# LIDO-HW_100_VinAndPower.net
KiCad netlist of a schematic drawn in Altium Designer
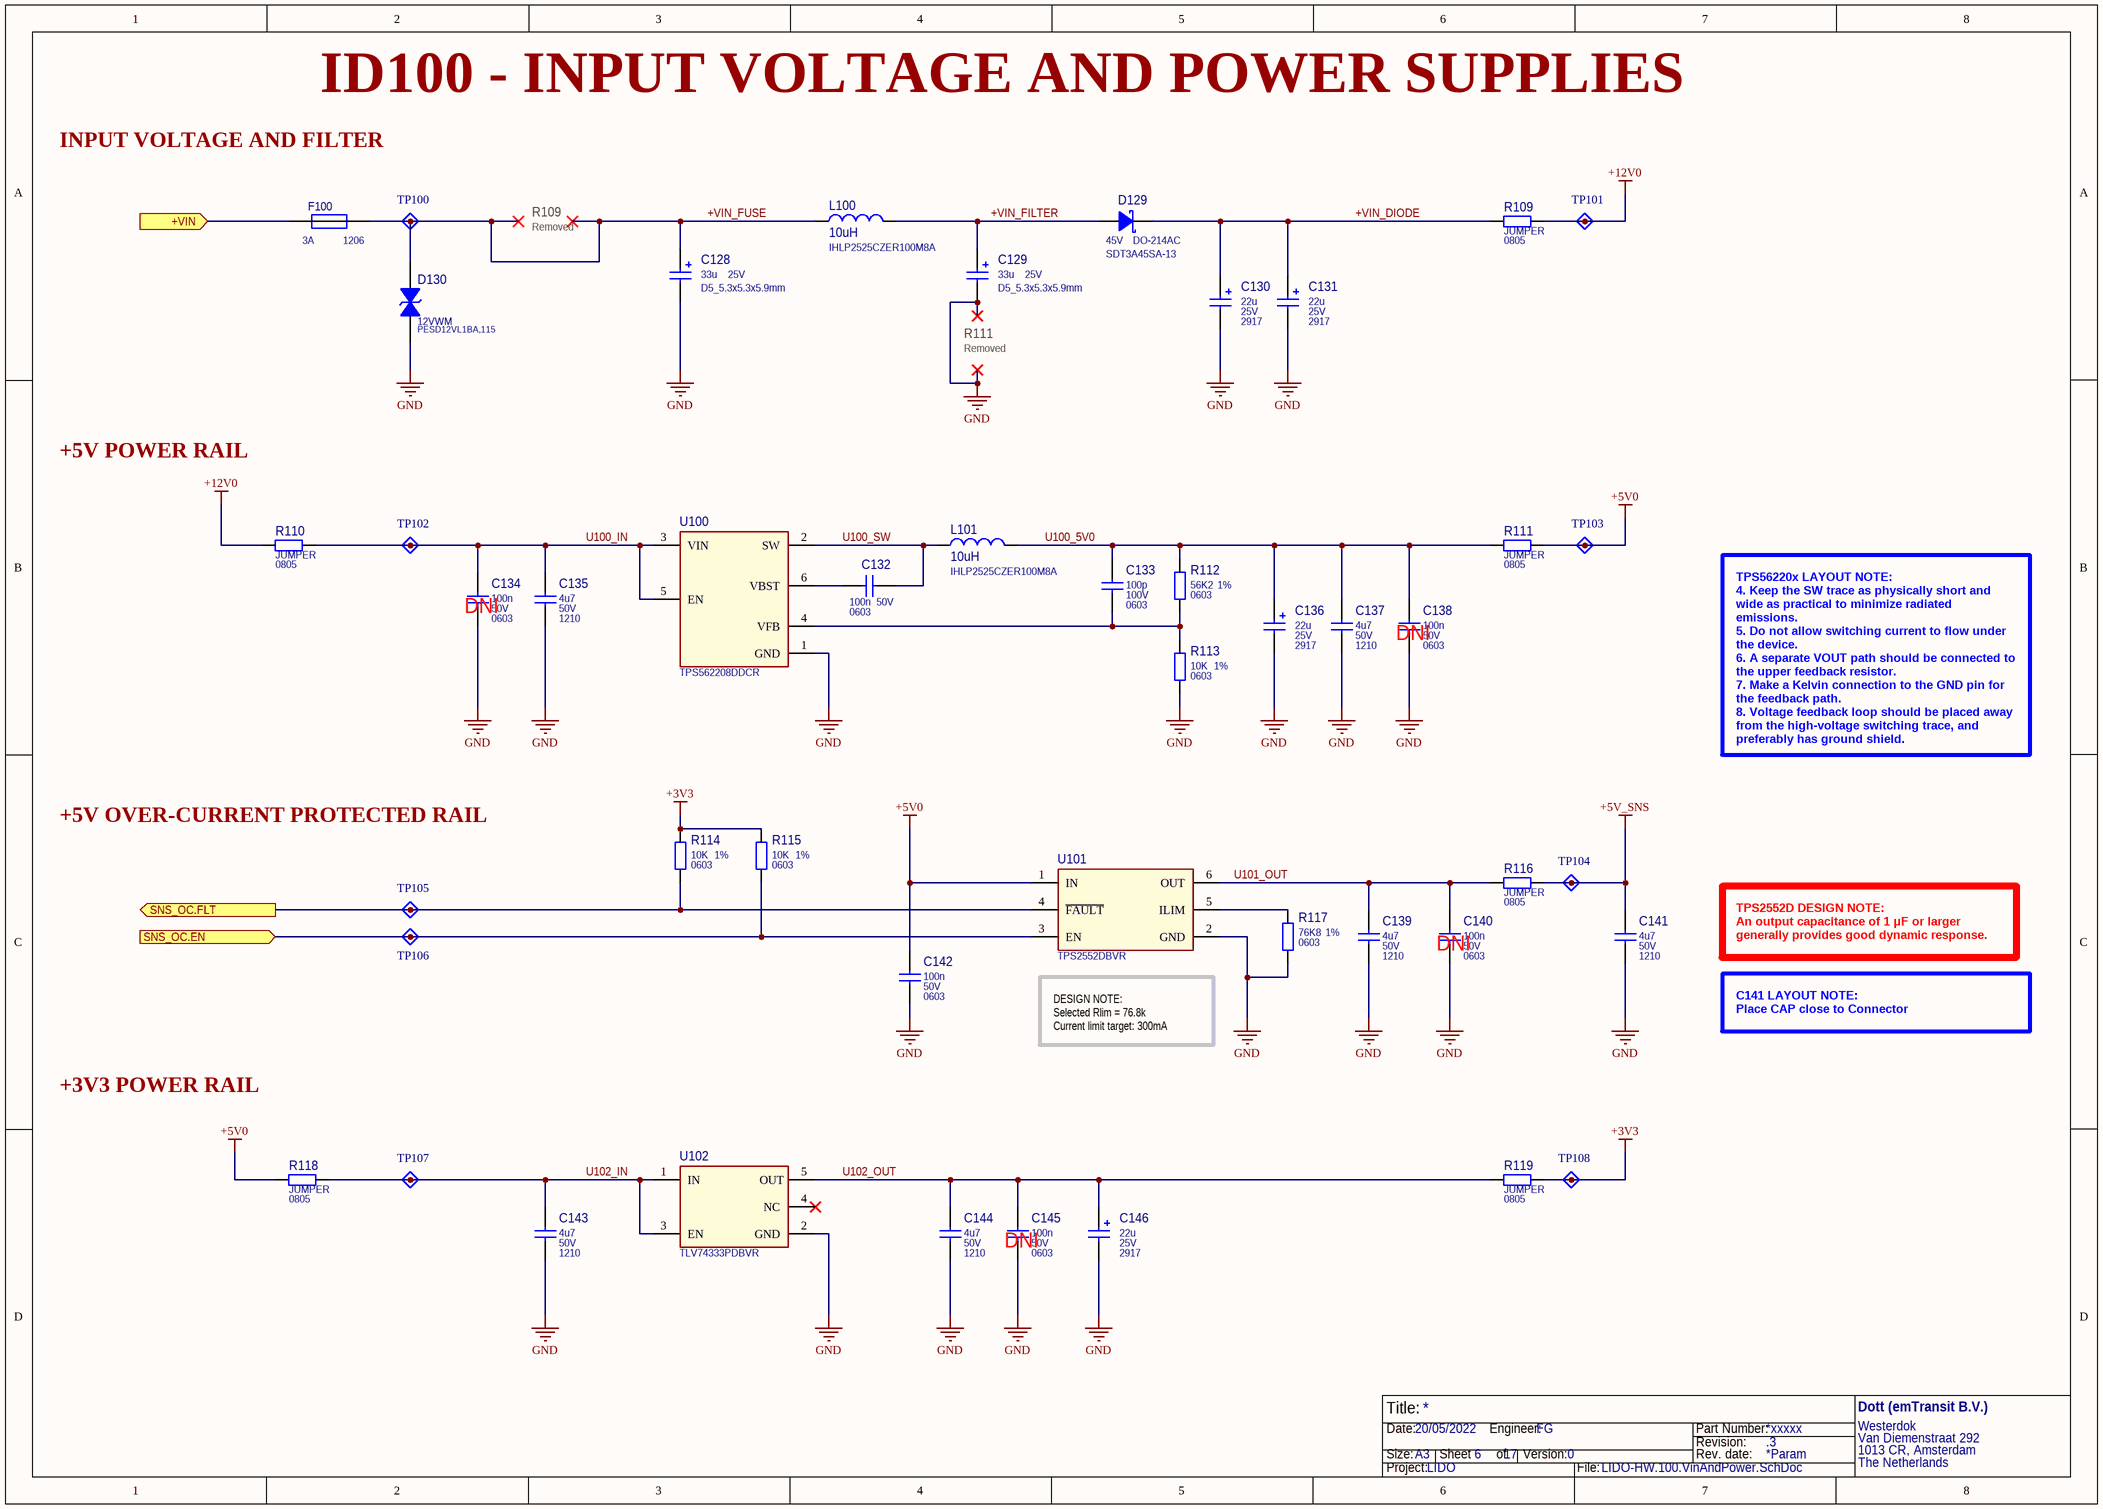
[diagram p0: LIDO-HW.100.VinAndPower.SchDoc]

(export (version "E")
  (design (tool "Eeschema 10.0.6"))
  (components
    (comp (ref "C128")
      (value "33u")
      (footprint "CAPAE_C_530X590L22X7-N_PANASONIC_A")
      (description "CAP ALUM POLY 33UF 20% 25V SMD")
      (fields
        (field (name "MANUFACTURER PART NUMBER") "25SVPK33M")
        (field (name "MANUFACTURER") "Panasonic Electronic Components")
        (field (name "PART VALUE 2") "25V")
        (field (name "PART PACKAGE") "D5_5.3x5.3x5.9mm")
      )
      (libsource (lib "DB_Library") (part "Polarized"))
    )
    (comp (ref "C129")
      (value "33u")
      (footprint "CAPAE_C_530X590L22X7-N_PANASONIC_A")
      (description "CAP ALUM POLY 33UF 20% 25V SMD")
      (fields
        (field (name "MANUFACTURER PART NUMBER") "25SVPK33M")
        (field (name "MANUFACTURER") "Panasonic Electronic Components")
        (field (name "PART VALUE 2") "25V")
        (field (name "PART PACKAGE") "D5_5.3x5.3x5.9mm")
      )
      (libsource (lib "DB_Library") (part "Polarized"))
    )
    (comp (ref "C130")
      (value "22u")
      (footprint "CAP_2917_7343X140-N_MURATA_A")
      (description "CAP ALUM POLY 22UF 20% 25V SMD")
      (fields
        (field (name "MANUFACTURER PART NUMBER") "ECASD31E226M040KA0")
        (field (name "MANUFACTURER") "Murata Electronics")
        (field (name "PART VALUE 2") "25V")
        (field (name "PART PACKAGE") "2917")
      )
      (libsource (lib "DB_Library") (part "Polarized"))
    )
    (comp (ref "C131")
      (value "22u")
      (footprint "CAP_2917_7343X140-N_MURATA_A")
      (description "CAP ALUM POLY 22UF 20% 25V SMD")
      (fields
        (field (name "MANUFACTURER PART NUMBER") "ECASD31E226M040KA0")
        (field (name "MANUFACTURER") "Murata Electronics")
        (field (name "PART VALUE 2") "25V")
        (field (name "PART PACKAGE") "2917")
      )
      (libsource (lib "DB_Library") (part "Polarized"))
    )
    (comp (ref "C132")
      (value "100n")
      (footprint "CAP_0603_1608X90-N_MURATA_A")
      (description "CAP CER 0.1UF 50V X7R 0603")
      (fields
        (field (name "MANUFACTURER PART NUMBER") "CGA3E2X7R1H104K080AA")
        (field (name "MANUFACTURER") "TDK Corporation")
        (field (name "PART VALUE 2") "50V")
        (field (name "PART PACKAGE") "0603")
      )
      (libsource (lib "DB_Library") (part "Ceramic"))
    )
    (comp (ref "C133")
      (value "100p")
      (footprint "CAP_0603_1608X90-N_MURATA_A")
      (description "CAP CER 100PF 100V C0G 0603")
      (fields
        (field (name "MANUFACTURER PART NUMBER") "CGA3E2C0G2A101J080AA")
        (field (name "MANUFACTURER") "TDK Corporation")
        (field (name "PART VALUE 2") "100V")
        (field (name "PART PACKAGE") "0603")
      )
      (libsource (lib "DB_Library") (part "Ceramic"))
    )
    (comp (ref "C134")
      (value "100n")
      (footprint "CAP_0603_1608X90-N_MURATA_A")
      (description "CAP CER 0.1UF 50V X7R 0603")
      (fields
        (field (name "MANUFACTURER PART NUMBER") "CGA3E2X7R1H104K080AA")
        (field (name "MANUFACTURER") "TDK Corporation")
        (field (name "PART VALUE 2") "50V")
        (field (name "PART PACKAGE") "0603")
      )
      (libsource (lib "DB_Library") (part "Ceramic"))
    )
    (comp (ref "C135")
      (value "4u7")
      (footprint "CAP_1210_3225X180-N_MURATA_A")
      (description "CAP CER 4.7UF 50V X7R 1210")
      (fields
        (field (name "MANUFACTURER PART NUMBER") "CL32B475KBJVPNE")
        (field (name "MANUFACTURER") "Samsung Electro-Mechanics")
        (field (name "PART VALUE 2") "50V")
        (field (name "PART PACKAGE") "1210")
      )
      (libsource (lib "DB_Library") (part "Ceramic"))
    )
    (comp (ref "C136")
      (value "22u")
      (footprint "CAP_2917_7343X140-N_MURATA_A")
      (description "CAP ALUM POLY 22UF 20% 25V SMD")
      (fields
        (field (name "MANUFACTURER PART NUMBER") "ECASD31E226M040KA0")
        (field (name "MANUFACTURER") "Murata Electronics")
        (field (name "PART VALUE 2") "25V")
        (field (name "PART PACKAGE") "2917")
      )
      (libsource (lib "DB_Library") (part "Polarized"))
    )
    (comp (ref "C137")
      (value "4u7")
      (footprint "CAP_1210_3225X180-N_MURATA_A")
      (description "CAP CER 4.7UF 50V X7R 1210")
      (fields
        (field (name "MANUFACTURER PART NUMBER") "CL32B475KBJVPNE")
        (field (name "MANUFACTURER") "Samsung Electro-Mechanics")
        (field (name "PART VALUE 2") "50V")
        (field (name "PART PACKAGE") "1210")
      )
      (libsource (lib "DB_Library") (part "Ceramic"))
    )
    (comp (ref "C138")
      (value "100n")
      (footprint "CAP_0603_1608X90-N_MURATA_A")
      (description "CAP CER 0.1UF 50V X7R 0603")
      (fields
        (field (name "MANUFACTURER PART NUMBER") "CGA3E2X7R1H104K080AA")
        (field (name "MANUFACTURER") "TDK Corporation")
        (field (name "PART VALUE 2") "50V")
        (field (name "PART PACKAGE") "0603")
      )
      (libsource (lib "DB_Library") (part "Ceramic"))
    )
    (comp (ref "C139")
      (value "4u7")
      (footprint "CAP_1210_3225X180-N_MURATA_A")
      (description "CAP CER 4.7UF 50V X7R 1210")
      (fields
        (field (name "MANUFACTURER PART NUMBER") "CL32B475KBJVPNE")
        (field (name "MANUFACTURER") "Samsung Electro-Mechanics")
        (field (name "PART VALUE 2") "50V")
        (field (name "PART PACKAGE") "1210")
      )
      (libsource (lib "DB_Library") (part "Ceramic"))
    )
    (comp (ref "C140")
      (value "100n")
      (footprint "CAP_0603_1608X90-N_MURATA_A")
      (description "CAP CER 0.1UF 50V X7R 0603")
      (fields
        (field (name "MANUFACTURER PART NUMBER") "CGA3E2X7R1H104K080AA")
        (field (name "MANUFACTURER") "TDK Corporation")
        (field (name "PART VALUE 2") "50V")
        (field (name "PART PACKAGE") "0603")
      )
      (libsource (lib "DB_Library") (part "Ceramic"))
    )
    (comp (ref "C141")
      (value "4u7")
      (footprint "CAP_1210_3225X180-N_MURATA_A")
      (description "CAP CER 4.7UF 50V X7R 1210")
      (fields
        (field (name "MANUFACTURER PART NUMBER") "CL32B475KBJVPNE")
        (field (name "MANUFACTURER") "Samsung Electro-Mechanics")
        (field (name "PART VALUE 2") "50V")
        (field (name "PART PACKAGE") "1210")
      )
      (libsource (lib "DB_Library") (part "Ceramic"))
    )
    (comp (ref "C142")
      (value "100n")
      (footprint "CAP_0603_1608X90-N_MURATA_A")
      (description "CAP CER 0.1UF 50V X7R 0603")
      (fields
        (field (name "MANUFACTURER PART NUMBER") "CGA3E2X7R1H104K080AA")
        (field (name "MANUFACTURER") "TDK Corporation")
        (field (name "PART VALUE 2") "50V")
        (field (name "PART PACKAGE") "0603")
      )
      (libsource (lib "DB_Library") (part "Ceramic"))
    )
    (comp (ref "C143")
      (value "4u7")
      (footprint "CAP_1210_3225X180-N_MURATA_A")
      (description "CAP CER 4.7UF 50V X7R 1210")
      (fields
        (field (name "MANUFACTURER PART NUMBER") "CL32B475KBJVPNE")
        (field (name "MANUFACTURER") "Samsung Electro-Mechanics")
        (field (name "PART VALUE 2") "50V")
        (field (name "PART PACKAGE") "1210")
      )
      (libsource (lib "DB_Library") (part "Ceramic"))
    )
    (comp (ref "C144")
      (value "4u7")
      (footprint "CAP_1210_3225X180-N_MURATA_A")
      (description "CAP CER 4.7UF 50V X7R 1210")
      (fields
        (field (name "MANUFACTURER PART NUMBER") "CL32B475KBJVPNE")
        (field (name "MANUFACTURER") "Samsung Electro-Mechanics")
        (field (name "PART VALUE 2") "50V")
        (field (name "PART PACKAGE") "1210")
      )
      (libsource (lib "DB_Library") (part "Ceramic"))
    )
    (comp (ref "C145")
      (value "100n")
      (footprint "CAP_0603_1608X90-N_MURATA_A")
      (description "CAP CER 0.1UF 50V X7R 0603")
      (fields
        (field (name "MANUFACTURER PART NUMBER") "CGA3E2X7R1H104K080AA")
        (field (name "MANUFACTURER") "TDK Corporation")
        (field (name "PART VALUE 2") "50V")
        (field (name "PART PACKAGE") "0603")
      )
      (libsource (lib "DB_Library") (part "Ceramic"))
    )
    (comp (ref "C146")
      (value "22u")
      (footprint "CAP_2917_7343X140-N_MURATA_A")
      (description "CAP ALUM POLY 22UF 20% 25V SMD")
      (fields
        (field (name "MANUFACTURER PART NUMBER") "ECASD31E226M040KA0")
        (field (name "MANUFACTURER") "Murata Electronics")
        (field (name "PART VALUE 2") "25V")
        (field (name "PART PACKAGE") "2917")
      )
      (libsource (lib "DB_Library") (part "Polarized"))
    )
    (comp (ref "D129")
      (value "45V")
      (footprint "DIOM519X260X240L114X145-N_WURTH_A")
      (description "SCHOTTKY RECTIFIER SMA T&R 10K")
      (fields
        (field (name "MANUFACTURER PART NUMBER") "SDT3A45SA-13")
        (field (name "MANUFACTURER") "Diodes Incorporated")
        (field (name "PART PACKAGE") "DO-214AC")
        (field (name "OBSOLETE PART") "False")
      )
      (libsource (lib "DB_Library") (part "Schottky_A"))
    )
    (comp (ref "D130")
      (value "12VWM")
      (footprint "NXP_SOD-323_250X125X95L30x32_A")
      (description "37V Clamp 5A (8/20µs) Ipp Tvs Diode Surface Mount SOD-323")
      (fields
        (field (name "MANUFACTURER PART NUMBER") "PESD12VL1BA,115")
        (field (name "MANUFACTURER") "Nexperia USA Inc.")
        (field (name "PART VALUE") "12VWM")
        (field (name "OBSOLETE PART") "False")
      )
      (libsource (lib "DB_Library") (part "BI-TVS_DIODE_B"))
    )
    (comp (ref "F100")
      (value "3A")
      (footprint "FUSE_1206-N_YAGEO_A")
      (description "3 A 125 V AC 63 V DC Fuse Board Mount (Cartridge Style Excluded) Surface Mount 1206 (3216 Metric)")
      (fields
        (field (name "MANUFACTURER PART NUMBER") "C1Q 3")
        (field (name "MANUFACTURER") "Bel Fuse Inc.")
        (field (name "PART PACKAGE") "1206")
      )
      (libsource (lib "DB_Library") (part "Fuse"))
    )
    (comp (ref "L100")
      (value "10uH")
      (footprint "VISHAY_IHLP2525CZ_647X647X300_A")
      (description "FIXED IND 10UH 4A 76.9 MOHM SMD")
      (fields
        (field (name "MANUFACTURER PART NUMBER") "IHLP2525CZER100M8A")
        (field (name "MANUFACTURER") "Vishay Dale")
        (field (name "OBSOLETE PART") "False")
      )
      (libsource (lib "DB_Library") (part "Inductor"))
    )
    (comp (ref "L101")
      (value "10uH")
      (footprint "VISHAY_IHLP2525CZ_647X647X300_A")
      (description "FIXED IND 10UH 4A 76.9 MOHM SMD")
      (fields
        (field (name "MANUFACTURER PART NUMBER") "IHLP2525CZER100M8A")
        (field (name "MANUFACTURER") "Vishay Dale")
        (field (name "OBSOLETE PART") "False")
      )
      (libsource (lib "DB_Library") (part "Inductor"))
    )
    (comp (ref "R109")
      (value "JUMPER")
      (footprint "RES_0805_2012X65-N_YAGEO_A")
      (description "RES SMD 0 OHM JUMPER 1/8W 0805")
      (fields
        (field (name "MANUFACTURER PART NUMBER") "ERJ-6GEY0R00V")
        (field (name "MANUFACTURER") "Panasonic Electronic Components")
        (field (name "PART PACKAGE") "0805")
      )
      (libsource (lib "") (part "Resistor_1"))
    )
    (comp (ref "R110")
      (value "JUMPER")
      (footprint "RES_0805_2012X65-N_YAGEO_A")
      (description "RES SMD 0 OHM JUMPER 1/8W 0805")
      (fields
        (field (name "MANUFACTURER PART NUMBER") "ERJ-6GEY0R00V")
        (field (name "MANUFACTURER") "Panasonic Electronic Components")
        (field (name "PART PACKAGE") "0805")
      )
      (libsource (lib "") (part "Resistor_1"))
    )
    (comp (ref "R111")
      (value "JUMPER")
      (footprint "RES_0805_2012X65-N_YAGEO_A")
      (description "RES SMD 0 OHM JUMPER 1/8W 0805")
      (fields
        (field (name "MANUFACTURER PART NUMBER") "ERJ-6GEY0R00V")
        (field (name "MANUFACTURER") "Panasonic Electronic Components")
        (field (name "PART PACKAGE") "0805")
      )
      (libsource (lib "") (part "Resistor_1"))
    )
    (comp (ref "R112")
      (value "56K2")
      (footprint "RES_0603_1608X60-N_YAGEO_A")
      (description "RES SMD 56.2K OHM 1% 1/10W 0603")
      (fields
        (field (name "MANUFACTURER PART NUMBER") "ERJ-3EKF5622V")
        (field (name "MANUFACTURER") "Panasonic Electronic Components")
        (field (name "PART VALUE 2") "1%")
        (field (name "PART PACKAGE") "0603")
      )
      (libsource (lib "DB_Library") (part "Resistor"))
    )
    (comp (ref "R113")
      (value "10K")
      (footprint "RES_0603_1608X60-N_YAGEO_A")
      (description "RES 10K OHM 1% 1/10W 0603")
      (fields
        (field (name "MANUFACTURER PART NUMBER") "RC0603FR-0710KL")
        (field (name "MANUFACTURER") "YAGEO")
        (field (name "PART VALUE 2") "1%")
        (field (name "PART PACKAGE") "0603")
      )
      (libsource (lib "DB_Library") (part "Resistor"))
    )
    (comp (ref "R114")
      (value "10K")
      (footprint "RES_0603_1608X60-N_YAGEO_A")
      (description "RES 10K OHM 1% 1/10W 0603")
      (fields
        (field (name "MANUFACTURER PART NUMBER") "RC0603FR-0710KL")
        (field (name "MANUFACTURER") "YAGEO")
        (field (name "PART VALUE 2") "1%")
        (field (name "PART PACKAGE") "0603")
      )
      (libsource (lib "DB_Library") (part "Resistor"))
    )
    (comp (ref "R115")
      (value "10K")
      (footprint "RES_0603_1608X60-N_YAGEO_A")
      (description "RES 10K OHM 1% 1/10W 0603")
      (fields
        (field (name "MANUFACTURER PART NUMBER") "RC0603FR-0710KL")
        (field (name "MANUFACTURER") "YAGEO")
        (field (name "PART VALUE 2") "1%")
        (field (name "PART PACKAGE") "0603")
      )
      (libsource (lib "DB_Library") (part "Resistor"))
    )
    (comp (ref "R116")
      (value "JUMPER")
      (footprint "RES_0805_2012X65-N_YAGEO_A")
      (description "RES SMD 0 OHM JUMPER 1/8W 0805")
      (fields
        (field (name "MANUFACTURER PART NUMBER") "ERJ-6GEY0R00V")
        (field (name "MANUFACTURER") "Panasonic Electronic Components")
        (field (name "PART PACKAGE") "0805")
      )
      (libsource (lib "") (part "Resistor_1"))
    )
    (comp (ref "R117")
      (value "76K8")
      (footprint "RES_0603_1608X60-N_YAGEO_A")
      (description "RES SMD 76.8K OHM 1% 1/10W 0603")
      (fields
        (field (name "MANUFACTURER PART NUMBER") "ERJ-3EKF7682V")
        (field (name "MANUFACTURER") "Panasonic Electronic Components")
        (field (name "PART VALUE 2") "1%")
        (field (name "PART PACKAGE") "0603")
      )
      (libsource (lib "DB_Library") (part "Resistor"))
    )
    (comp (ref "R118")
      (value "JUMPER")
      (footprint "RES_0805_2012X65-N_YAGEO_A")
      (description "RES SMD 0 OHM JUMPER 1/8W 0805")
      (fields
        (field (name "MANUFACTURER PART NUMBER") "ERJ-6GEY0R00V")
        (field (name "MANUFACTURER") "Panasonic Electronic Components")
        (field (name "PART PACKAGE") "0805")
      )
      (libsource (lib "") (part "Resistor_1"))
    )
    (comp (ref "R119")
      (value "JUMPER")
      (footprint "RES_0805_2012X65-N_YAGEO_A")
      (description "RES SMD 0 OHM JUMPER 1/8W 0805")
      (fields
        (field (name "MANUFACTURER PART NUMBER") "ERJ-6GEY0R00V")
        (field (name "MANUFACTURER") "Panasonic Electronic Components")
        (field (name "PART PACKAGE") "0805")
      )
      (libsource (lib "") (part "Resistor_1"))
    )
    (comp (ref "TP100")
      (value "TestPoint_A")
      (footprint "TESTPOINT_1D_A")
      (description "Pad Diamater 1mm")
      (fields (field (name "PART") "Test Point 1D A") (field (name "OBSOLETE PART") "False"))
      (libsource (lib "DB_Library") (part "TestPoint_A"))
    )
    (comp (ref "TP101")
      (value "TestPoint_A")
      (footprint "TESTPOINT_1D_A")
      (description "Pad Diamater 1mm")
      (fields (field (name "PART") "Test Point 1D A") (field (name "OBSOLETE PART") "False"))
      (libsource (lib "DB_Library") (part "TestPoint_A"))
    )
    (comp (ref "TP102")
      (value "TestPoint_A")
      (footprint "TESTPOINT_1D_A")
      (description "Pad Diamater 1mm")
      (fields (field (name "PART") "Test Point 1D A") (field (name "OBSOLETE PART") "False"))
      (libsource (lib "DB_Library") (part "TestPoint_A"))
    )
    (comp (ref "TP103")
      (value "TestPoint_A")
      (footprint "TESTPOINT_1D_A")
      (description "Pad Diamater 1mm")
      (fields (field (name "PART") "Test Point 1D A") (field (name "OBSOLETE PART") "False"))
      (libsource (lib "DB_Library") (part "TestPoint_A"))
    )
    (comp (ref "TP104")
      (value "TestPoint_A")
      (footprint "TESTPOINT_1D_A")
      (description "Pad Diamater 1mm")
      (fields (field (name "PART") "Test Point 1D A") (field (name "OBSOLETE PART") "False"))
      (libsource (lib "DB_Library") (part "TestPoint_A"))
    )
    (comp (ref "TP105")
      (value "TestPoint_A")
      (footprint "TESTPOINT_1D_A")
      (description "Pad Diamater 1mm")
      (fields (field (name "PART") "Test Point 1D A") (field (name "OBSOLETE PART") "False"))
      (libsource (lib "DB_Library") (part "TestPoint_A"))
    )
    (comp (ref "TP106")
      (value "TestPoint_A")
      (footprint "TESTPOINT_1D_A")
      (description "Pad Diamater 1mm")
      (fields (field (name "PART") "Test Point 1D A") (field (name "OBSOLETE PART") "False"))
      (libsource (lib "DB_Library") (part "TestPoint_A"))
    )
    (comp (ref "TP107")
      (value "TestPoint_A")
      (footprint "TESTPOINT_1D_A")
      (description "Pad Diamater 1mm")
      (fields (field (name "PART") "Test Point 1D A") (field (name "OBSOLETE PART") "False"))
      (libsource (lib "DB_Library") (part "TestPoint_A"))
    )
    (comp (ref "TP108")
      (value "TestPoint_A")
      (footprint "TESTPOINT_1D_A")
      (description "Pad Diamater 1mm")
      (fields (field (name "PART") "Test Point 1D A") (field (name "OBSOLETE PART") "False"))
      (libsource (lib "DB_Library") (part "TestPoint_A"))
    )
    (comp (ref "U100")
      (value "TPS562208DDCR")
      (footprint "SOT23-6P95_280X145L45-N_MICROCHIP_A")
      (description "Buck Switching Regulator IC Positive Adjustable 0.768V 1 Output 2A SOT-23-6 Thin, TSOT-23-6")
      (fields (field (name "MANUFACTURER") "Texas Instruments") (field (name "OBSOLETE PART") "False"))
      (libsource (lib "DB_Library") (part "TPS562208_A"))
    )
    (comp (ref "U101")
      (value "TPS2552DBVR")
      (footprint "SOT23-6P95_280X145L45-N_MICROCHIP_A")
      (description "Power Switch/Driver 1:1 N-Channel 1.5A SOT-23-6")
      (fields (field (name "MANUFACTURER") "Texas Instruments") (field (name "OBSOLETE PART") "False"))
      (libsource (lib "DB_Library") (part "TPS2552_A"))
    )
    (comp (ref "U102")
      (value "TLV74333PDBVR")
      (footprint "SOT23-5P95_280X145L45-N_TI_A")
      (description "Linear Voltage Regulator IC Positive Fixed 1 Output 300mA SOT-23-5")
      (fields (field (name "MANUFACTURER") "Texas Instruments") (field (name "OBSOLETE PART") "False"))
      (libsource (lib "DB_Library") (part "TLV74333PD_A"))
    )
  )
  (nets
    (net (code "1") (name "+3V3") (class "Default")
      (node (ref "R114") (pin "2") (pinfunction "2_2") (pintype "passive"))
      (node (ref "R115") (pin "2") (pinfunction "2_2") (pintype "passive"))
      (node (ref "R119") (pin "2") (pinfunction "2_2") (pintype "passive"))
      (node (ref "TP108") (pin "1") (pinfunction "TP_1") (pintype "passive"))
    )
    (net (code "2") (name "+5V0") (class "Default")
      (node (ref "C142") (pin "2") (pinfunction "2_2") (pintype "passive"))
      (node (ref "R111") (pin "2") (pinfunction "2_2") (pintype "passive"))
      (node (ref "R118") (pin "1") (pinfunction "1_1") (pintype "passive"))
      (node (ref "TP103") (pin "1") (pinfunction "TP_1") (pintype "passive"))
      (node (ref "U101") (pin "1") (pinfunction "IN_1") (pintype "power_in"))
    )
    (net (code "3") (name "+5V_SNS") (class "Default")
      (node (ref "C141") (pin "1") (pinfunction "1_1") (pintype "passive"))
      (node (ref "R116") (pin "2") (pinfunction "2_2") (pintype "passive"))
      (node (ref "TP104") (pin "1") (pinfunction "TP_1") (pintype "passive"))
    )
    (net (code "4") (name "+12V0") (class "Default")
      (node (ref "R109") (pin "2") (pinfunction "2_2") (pintype "passive"))
      (node (ref "R110") (pin "1") (pinfunction "1_1") (pintype "passive"))
      (node (ref "TP101") (pin "1") (pinfunction "TP_1") (pintype "passive"))
    )
    (net (code "5") (name "/+VIN") (class "Default")
      (node (ref "F100") (pin "1") (pinfunction "1_1") (pintype "passive"))
    )
    (net (code "6") (name "/+VIN_DIODE") (class "Default")
      (node (ref "C130") (pin "1") (pinfunction "1_1") (pintype "passive"))
      (node (ref "C131") (pin "1") (pinfunction "1_1") (pintype "passive"))
      (node (ref "D129") (pin "C") (pinfunction "C_C") (pintype "passive"))
      (node (ref "R109") (pin "1") (pinfunction "1_1") (pintype "passive"))
    )
    (net (code "7") (name "/+VIN_FILTER") (class "Default")
      (node (ref "C129") (pin "1") (pinfunction "1_1") (pintype "passive"))
      (node (ref "D129") (pin "A") (pinfunction "A_A") (pintype "passive"))
      (node (ref "L100") (pin "2") (pinfunction "2_2") (pintype "passive"))
    )
    (net (code "8") (name "/+VIN_FUSE") (class "Default")
      (node (ref "C128") (pin "1") (pinfunction "1_1") (pintype "passive"))
      (node (ref "D130") (pin "A") (pinfunction "A_A") (pintype "passive"))
      (node (ref "F100") (pin "2") (pinfunction "2_2") (pintype "passive"))
      (node (ref "L100") (pin "1") (pinfunction "1_1") (pintype "passive"))
      (node (ref "TP100") (pin "1") (pinfunction "TP_1") (pintype "passive"))
    )
    (net (code "9") (name "/SNS_OC.EN") (class "Default")
      (node (ref "R115") (pin "1") (pinfunction "1_1") (pintype "passive"))
      (node (ref "TP106") (pin "1") (pinfunction "TP_1") (pintype "passive"))
      (node (ref "U101") (pin "3") (pinfunction "EN_3") (pintype "passive"))
    )
    (net (code "10") (name "/SNS_OC.FLT") (class "Default")
      (node (ref "R114") (pin "1") (pinfunction "1_1") (pintype "passive"))
      (node (ref "TP105") (pin "1") (pinfunction "TP_1") (pintype "passive"))
      (node (ref "U101") (pin "4") (pinfunction "~{FAULT}_4") (pintype "passive"))
    )
    (net (code "11") (name "/U100_5V0") (class "Default")
      (node (ref "C133") (pin "1") (pinfunction "1_1") (pintype "passive"))
      (node (ref "C136") (pin "1") (pinfunction "1_1") (pintype "passive"))
      (node (ref "C137") (pin "1") (pinfunction "1_1") (pintype "passive"))
      (node (ref "C138") (pin "2") (pinfunction "2_2") (pintype "passive"))
      (node (ref "L101") (pin "2") (pinfunction "2_2") (pintype "passive"))
      (node (ref "R111") (pin "1") (pinfunction "1_1") (pintype "passive"))
      (node (ref "R112") (pin "2") (pinfunction "2_2") (pintype "passive"))
    )
    (net (code "12") (name "/U100_IN") (class "Default")
      (node (ref "C134") (pin "2") (pinfunction "2_2") (pintype "passive"))
      (node (ref "C135") (pin "1") (pinfunction "1_1") (pintype "passive"))
      (node (ref "R110") (pin "2") (pinfunction "2_2") (pintype "passive"))
      (node (ref "TP102") (pin "1") (pinfunction "TP_1") (pintype "passive"))
      (node (ref "U100") (pin "3") (pinfunction "VIN_3") (pintype "power_in"))
      (node (ref "U100") (pin "5") (pinfunction "EN_5") (pintype "passive"))
    )
    (net (code "13") (name "/U100_SW") (class "Default")
      (node (ref "C132") (pin "2") (pinfunction "2_2") (pintype "passive"))
      (node (ref "L101") (pin "1") (pinfunction "1_1") (pintype "passive"))
      (node (ref "U100") (pin "2") (pinfunction "SW_2") (pintype "passive"))
    )
    (net (code "14") (name "/U101_OUT") (class "Default")
      (node (ref "C139") (pin "1") (pinfunction "1_1") (pintype "passive"))
      (node (ref "C140") (pin "2") (pinfunction "2_2") (pintype "passive"))
      (node (ref "R116") (pin "1") (pinfunction "1_1") (pintype "passive"))
      (node (ref "U101") (pin "6") (pinfunction "OUT_6") (pintype "power_in"))
    )
    (net (code "15") (name "/U102_IN") (class "Default")
      (node (ref "C143") (pin "1") (pinfunction "1_1") (pintype "passive"))
      (node (ref "R118") (pin "2") (pinfunction "2_2") (pintype "passive"))
      (node (ref "TP107") (pin "1") (pinfunction "TP_1") (pintype "passive"))
      (node (ref "U102") (pin "1") (pinfunction "IN_1") (pintype "power_in"))
      (node (ref "U102") (pin "3") (pinfunction "EN_3") (pintype "passive"))
    )
    (net (code "16") (name "/U102_OUT") (class "Default")
      (node (ref "C144") (pin "1") (pinfunction "1_1") (pintype "passive"))
      (node (ref "C145") (pin "2") (pinfunction "2_2") (pintype "passive"))
      (node (ref "C146") (pin "1") (pinfunction "1_1") (pintype "passive"))
      (node (ref "R119") (pin "1") (pinfunction "1_1") (pintype "passive"))
      (node (ref "U102") (pin "5") (pinfunction "OUT_5") (pintype "power_in"))
    )
    (net (code "17") (name "GND") (class "Default")
      (node (ref "C128") (pin "2") (pinfunction "2_2") (pintype "passive"))
      (node (ref "C129") (pin "2") (pinfunction "2_2") (pintype "passive"))
      (node (ref "C130") (pin "2") (pinfunction "2_2") (pintype "passive"))
      (node (ref "C131") (pin "2") (pinfunction "2_2") (pintype "passive"))
      (node (ref "C134") (pin "1") (pinfunction "1_1") (pintype "passive"))
      (node (ref "C135") (pin "2") (pinfunction "2_2") (pintype "passive"))
      (node (ref "C136") (pin "2") (pinfunction "2_2") (pintype "passive"))
      (node (ref "C137") (pin "2") (pinfunction "2_2") (pintype "passive"))
      (node (ref "C138") (pin "1") (pinfunction "1_1") (pintype "passive"))
      (node (ref "C139") (pin "2") (pinfunction "2_2") (pintype "passive"))
      (node (ref "C140") (pin "1") (pinfunction "1_1") (pintype "passive"))
      (node (ref "C141") (pin "2") (pinfunction "2_2") (pintype "passive"))
      (node (ref "C142") (pin "1") (pinfunction "1_1") (pintype "passive"))
      (node (ref "C143") (pin "2") (pinfunction "2_2") (pintype "passive"))
      (node (ref "C144") (pin "2") (pinfunction "2_2") (pintype "passive"))
      (node (ref "C145") (pin "1") (pinfunction "1_1") (pintype "passive"))
      (node (ref "C146") (pin "2") (pinfunction "2_2") (pintype "passive"))
      (node (ref "D130") (pin "C") (pinfunction "C_C") (pintype "passive"))
      (node (ref "R113") (pin "1") (pinfunction "1_1") (pintype "passive"))
      (node (ref "R117") (pin "1") (pinfunction "1_1") (pintype "passive"))
      (node (ref "U100") (pin "1") (pinfunction "GND_1") (pintype "power_in"))
      (node (ref "U101") (pin "2") (pinfunction "GND_2") (pintype "power_in"))
      (node (ref "U102") (pin "2") (pinfunction "GND_2") (pintype "power_in"))
    )
    (net (code "18") (name "Net-(U100-VBST)") (class "Default")
      (node (ref "C132") (pin "1") (pinfunction "1_1") (pintype "passive"))
      (node (ref "U100") (pin "6") (pinfunction "VBST_6") (pintype "passive"))
    )
    (net (code "19") (name "Net-(U100-VFB)") (class "Default")
      (node (ref "C133") (pin "2") (pinfunction "2_2") (pintype "passive"))
      (node (ref "R112") (pin "1") (pinfunction "1_1") (pintype "passive"))
      (node (ref "R113") (pin "2") (pinfunction "2_2") (pintype "passive"))
      (node (ref "U100") (pin "4") (pinfunction "VFB_4") (pintype "passive"))
    )
    (net (code "20") (name "Net-(U101-ILIM)") (class "Default")
      (node (ref "R117") (pin "2") (pinfunction "2_2") (pintype "passive"))
      (node (ref "U101") (pin "5") (pinfunction "ILIM_5") (pintype "passive"))
    )
    (net (code "21") (name "unconnected-(U102-NC-Pad4)") (class "Default")
      (node (ref "U102") (pin "4") (pinfunction "NC_4") (pintype "passive+no_connect"))
    )
  )
)
